# bits2.net
KiCad netlist of a schematic drawn in EAGLE
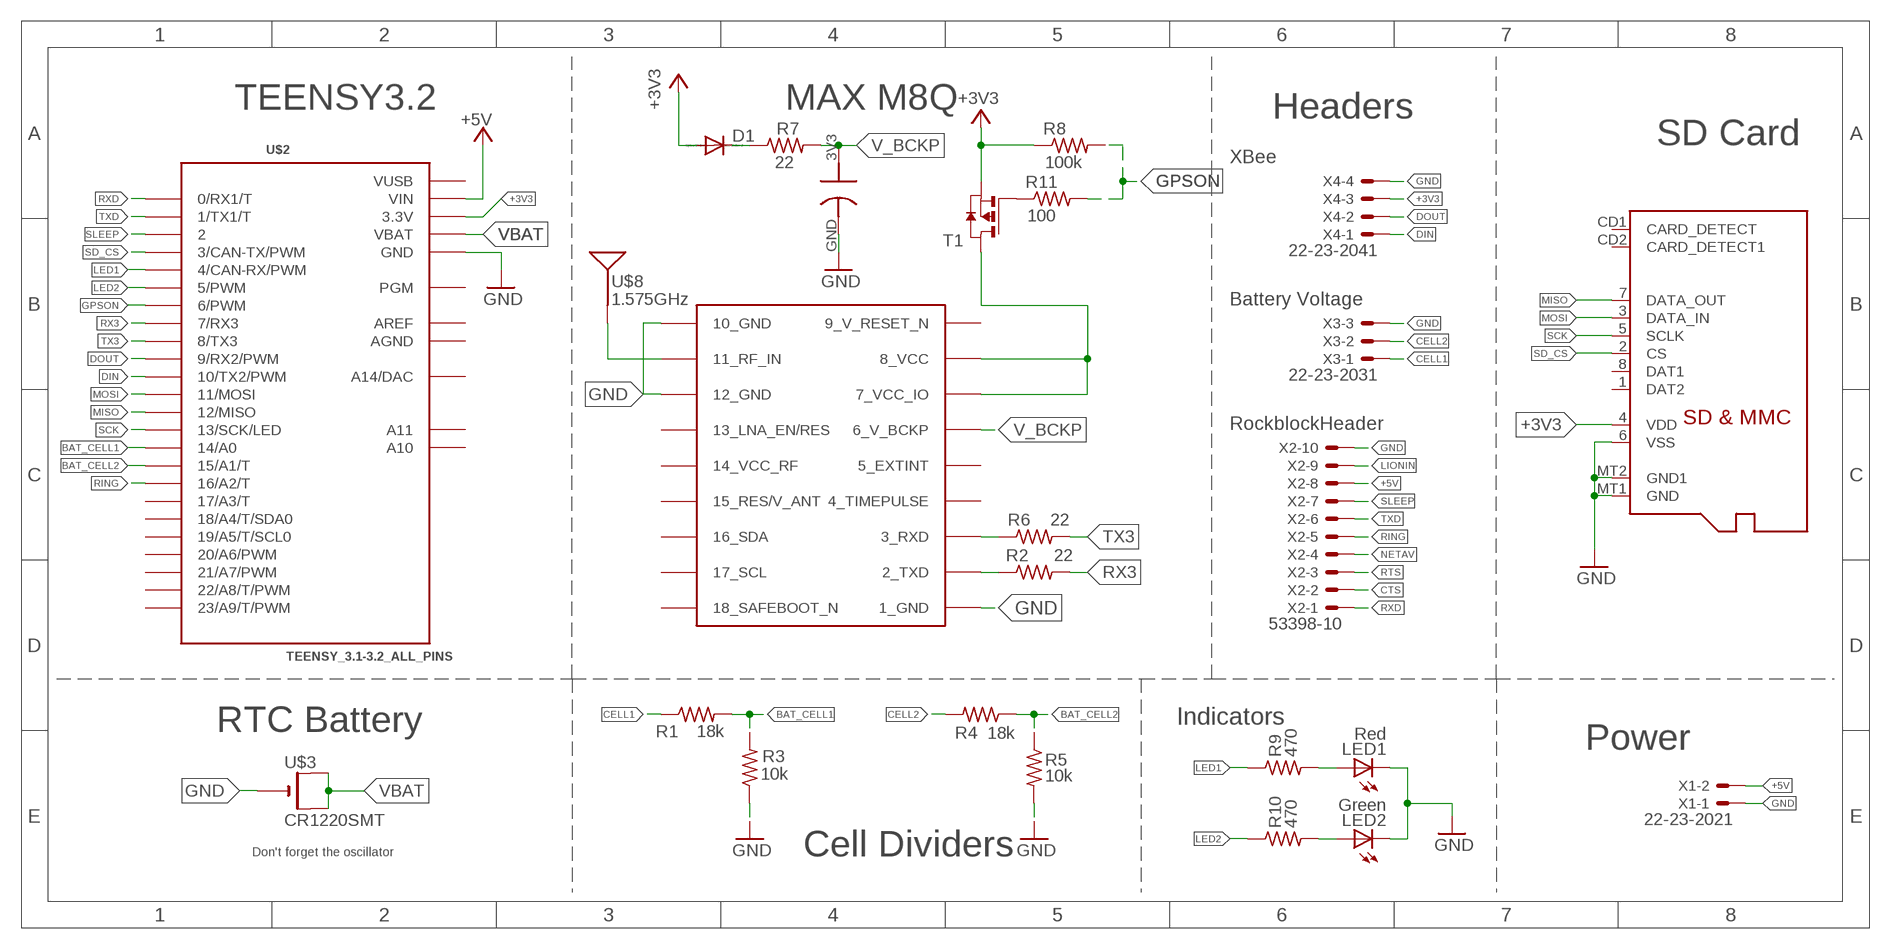
[diagram p0: schematic, sheet 1]

(export (version "E")
  (design (tool "Eeschema 10.0.6"))
  (components
    (comp (ref "C1")
      (value "DCK-3R3E204T614-E")
      (footprint "eagle-import:ELNASUPERCAP")
      (libsource (lib "eagle-import") (part "DCK-3R3E204T614-E"))
    )
    (comp (ref "D1")
      (value "DIODE-SOD523")
      (footprint "eagle-import:SOD523")
      (libsource (lib "eagle-import") (part "DIODE-SOD523"))
    )
    (comp (ref "LED1")
      (value "Red")
      (footprint "eagle-import:CHIP-LED0603")
      (libsource (lib "eagle-import") (part "LEDCHIP-LED0603"))
    )
    (comp (ref "LED2")
      (value "Green")
      (footprint "eagle-import:CHIP-LED0603")
      (libsource (lib "eagle-import") (part "LEDCHIP-LED0603"))
    )
    (comp (ref "R1")
      (value "18k")
      (footprint "eagle-import:R0603")
      (libsource (lib "eagle-import") (part "resistor_348_R-US_R0603"))
    )
    (comp (ref "R2")
      (value "22")
      (footprint "eagle-import:R0603")
      (libsource (lib "eagle-import") (part "R-US_R0603"))
    )
    (comp (ref "R3")
      (value "10k")
      (footprint "eagle-import:R0603")
      (libsource (lib "eagle-import") (part "resistor_348_R-US_R0603"))
    )
    (comp (ref "R4")
      (value "18k")
      (footprint "eagle-import:R0603")
      (libsource (lib "eagle-import") (part "resistor_348_R-US_R0603"))
    )
    (comp (ref "R5")
      (value "10k")
      (footprint "eagle-import:R0603")
      (libsource (lib "eagle-import") (part "resistor_348_R-US_R0603"))
    )
    (comp (ref "R6")
      (value "22")
      (footprint "eagle-import:R0603")
      (libsource (lib "eagle-import") (part "R-US_R0603"))
    )
    (comp (ref "R7")
      (value "22")
      (footprint "eagle-import:R0603")
      (libsource (lib "eagle-import") (part "R-US_R0603"))
    )
    (comp (ref "R8")
      (value "100k")
      (footprint "eagle-import:R0603")
      (libsource (lib "eagle-import") (part "R-US_R0603"))
    )
    (comp (ref "R9")
      (value "470")
      (footprint "eagle-import:R0603")
      (libsource (lib "eagle-import") (part "resistor_348_R-US_R0603"))
    )
    (comp (ref "R10")
      (value "470")
      (footprint "eagle-import:R0603")
      (libsource (lib "eagle-import") (part "resistor_348_R-US_R0603"))
    )
    (comp (ref "R11")
      (value "100")
      (footprint "eagle-import:R0603")
      (libsource (lib "eagle-import") (part "R-US_R0603"))
    )
    (comp (ref "T1")
      (value "PMOSSOT23")
      (footprint "eagle-import:SOT-23")
      (libsource (lib "eagle-import") (part "PMOSSOT23"))
    )
    (comp (ref "U$1")
      (value "MICROSD")
      (footprint "eagle-import:MICROSD")
      (libsource (lib "eagle-import") (part "MICROSD"))
    )
    (comp (ref "U$2")
      (value "TEENSY_3.1-3.2_ALL_PINS")
      (footprint "eagle-import:TEENSY_3.0-3.2&LC_ALL_PINS")
      (libsource (lib "eagle-import") (part "TEENSY_3.1-3.2_ALL_PINS"))
    )
    (comp (ref "U$3")
      (value "CR1220SMT")
      (footprint "eagle-import:CR1220-SMD")
      (libsource (lib "eagle-import") (part "CR1220SMT"))
    )
    (comp (ref "U$7")
      (value "MAX-M8")
      (footprint "eagle-import:MAX-M8")
      (libsource (lib "eagle-import") (part "MAX-M8"))
    )
    (comp (ref "U$8")
      (value "1.575GHz")
      (footprint "eagle-import:SPARKFUN-GPS_ANT-GPS-2X7MM")
      (libsource (lib "eagle-import") (part "SPARKFUN-GPS_ANTENNAGPS-2X7MM"))
    )
    (comp (ref "X1")
      (value "22-23-2021")
      (footprint "eagle-import:22-23-2021")
      (fields (field (name "MF") "MOLEX"))
      (libsource (lib "eagle-import") (part "22-23-2021"))
    )
    (comp (ref "X2")
      (value "53398-10")
      (footprint "eagle-import:53398-10")
      (fields (field (name "MF") "MOLEX") (field (name "MPN") "53398-1071"))
      (libsource (lib "eagle-import") (part "53?-10398"))
    )
    (comp (ref "X3")
      (value "22-23-2031")
      (footprint "eagle-import:22-23-2031")
      (fields (field (name "MF") "MOLEX"))
      (libsource (lib "eagle-import") (part "22-23-2031"))
    )
    (comp (ref "X4")
      (value "22-23-2041")
      (footprint "eagle-import:22-23-2041")
      (fields (field (name "MF") "MOLEX"))
      (libsource (lib "eagle-import") (part "22-23-2041"))
    )
  )
  (nets
    (net (code "1") (name "+3V3") (class "Default")
      (node (ref "D1") (pin "A") (pinfunction "A_A") (pintype "passive"))
      (node (ref "R8") (pin "1") (pinfunction "1_1") (pintype "passive"))
      (node (ref "T1") (pin "2") (pinfunction "S_2") (pintype "passive"))
      (node (ref "U$1") (pin "4") (pinfunction "VDD_4") (pintype "power_in"))
      (node (ref "U$2") (pin "3.3V") (pinfunction "3.3V_3.3V") (pintype "power_in"))
      (node (ref "U$2") (pin "3.3V1") (pinfunction "3.3V_3.3V1") (pintype "power_in"))
      (node (ref "X4") (pin "3") (pinfunction "S_3") (pintype "passive"))
    )
    (net (code "2") (name "+5V") (class "Default")
      (node (ref "U$2") (pin "VIN") (pinfunction "VIN_VIN") (pintype "power_in"))
      (node (ref "X1") (pin "2") (pinfunction "S_2") (pintype "passive"))
      (node (ref "X2") (pin "8") (pinfunction "S_8") (pintype "passive"))
    )
    (net (code "3") (name "/9_V_RESET_N") (class "Default")
      (node (ref "U$7") (pin "9_RESET_N") (pinfunction "9_V_RESET_N_9_RESET_N") (pintype "power_in"))
    )
    (net (code "4") (name "/AGND") (class "Default")
      (node (ref "U$2") (pin "AGND") (pinfunction "AGND_AGND") (pintype "power_in"))
    )
    (net (code "5") (name "/AREF") (class "Default")
      (node (ref "U$2") (pin "AREF") (pinfunction "AREF_AREF") (pintype "power_in"))
    )
    (net (code "6") (name "/VUSB") (class "Default")
      (node (ref "U$2") (pin "VUSB") (pinfunction "VUSB_VUSB") (pintype "power_in"))
    )
    (net (code "7") (name "BAT_CELL1") (class "Default")
      (node (ref "R1") (pin "2") (pinfunction "2_2") (pintype "passive"))
      (node (ref "R3") (pin "2") (pinfunction "2_2") (pintype "passive"))
      (node (ref "U$2") (pin "14/A0") (pinfunction "14/A0_14/A0") (pintype "bidirectional"))
    )
    (net (code "8") (name "BAT_CELL2") (class "Default")
      (node (ref "R4") (pin "1") (pinfunction "1_1") (pintype "passive"))
      (node (ref "R5") (pin "1") (pinfunction "1_1") (pintype "passive"))
      (node (ref "U$2") (pin "15/A1") (pinfunction "15/A1/T_15/A1") (pintype "bidirectional"))
    )
    (net (code "9") (name "CELL1") (class "Default")
      (node (ref "R1") (pin "1") (pinfunction "1_1") (pintype "passive"))
      (node (ref "X3") (pin "1") (pinfunction "S_1") (pintype "passive"))
    )
    (net (code "10") (name "CELL2") (class "Default")
      (node (ref "R4") (pin "2") (pinfunction "2_2") (pintype "passive"))
      (node (ref "X3") (pin "2") (pinfunction "S_2") (pintype "passive"))
    )
    (net (code "11") (name "CTS") (class "Default")
      (node (ref "X2") (pin "2") (pinfunction "S_2") (pintype "passive"))
    )
    (net (code "12") (name "DIN") (class "Default")
      (node (ref "U$2") (pin "10") (pinfunction "10/TX2/PWM_10") (pintype "bidirectional"))
      (node (ref "X4") (pin "1") (pinfunction "S_1") (pintype "passive"))
    )
    (net (code "13") (name "DOUT") (class "Default")
      (node (ref "U$2") (pin "9") (pinfunction "9/RX2/PWM_9") (pintype "bidirectional"))
      (node (ref "X4") (pin "2") (pinfunction "S_2") (pintype "passive"))
    )
    (net (code "14") (name "GND") (class "Default")
      (node (ref "C1") (pin "GND") (pinfunction "GND_GND") (pintype "bidirectional"))
      (node (ref "LED1") (pin "C") (pinfunction "C_C") (pintype "passive"))
      (node (ref "LED2") (pin "C") (pinfunction "C_C") (pintype "passive"))
      (node (ref "R3") (pin "1") (pinfunction "1_1") (pintype "passive"))
      (node (ref "R5") (pin "2") (pinfunction "2_2") (pintype "passive"))
      (node (ref "U$1") (pin "6") (pinfunction "VSS_6") (pintype "power_in"))
      (node (ref "U$1") (pin "MT1") (pinfunction "GND_MT1") (pintype "power_in"))
      (node (ref "U$1") (pin "MT2") (pinfunction "GND1_MT2") (pintype "power_in"))
      (node (ref "U$2") (pin "GND") (pinfunction "GND_GND") (pintype "power_in"))
      (node (ref "U$2") (pin "GND1") (pinfunction "GND_GND1") (pintype "power_in"))
      (node (ref "U$3") (pin "-") (pinfunction "-_-") (pintype "passive"))
      (node (ref "U$7") (pin "10_GND") (pinfunction "10_GND_10_GND") (pintype "power_in"))
      (node (ref "U$7") (pin "12_GND") (pinfunction "12_GND_12_GND") (pintype "power_in"))
      (node (ref "U$7") (pin "1_GND") (pinfunction "1_GND_1_GND") (pintype "power_in"))
      (node (ref "X1") (pin "1") (pinfunction "S_1") (pintype "passive"))
      (node (ref "X2") (pin "10") (pinfunction "S_10") (pintype "passive"))
      (node (ref "X3") (pin "3") (pinfunction "S_3") (pintype "passive"))
      (node (ref "X4") (pin "4") (pinfunction "S_4") (pintype "passive"))
    )
    (net (code "15") (name "GPSON") (class "Default")
      (node (ref "R11") (pin "2") (pinfunction "2_2") (pintype "passive"))
      (node (ref "R8") (pin "2") (pinfunction "2_2") (pintype "passive"))
      (node (ref "U$2") (pin "6") (pinfunction "6/PWM_6") (pintype "bidirectional"))
    )
    (net (code "16") (name "LED1") (class "Default")
      (node (ref "R9") (pin "1") (pinfunction "1_1") (pintype "passive"))
      (node (ref "U$2") (pin "4") (pinfunction "4/CAN-RX/PWM_4") (pintype "bidirectional"))
    )
    (net (code "17") (name "LED2") (class "Default")
      (node (ref "R10") (pin "1") (pinfunction "1_1") (pintype "passive"))
      (node (ref "U$2") (pin "5") (pinfunction "5/PWM_5") (pintype "bidirectional"))
    )
    (net (code "18") (name "LIONIN") (class "Default")
      (node (ref "X2") (pin "9") (pinfunction "S_9") (pintype "passive"))
    )
    (net (code "19") (name "MISO") (class "Default")
      (node (ref "U$1") (pin "7") (pinfunction "DATA_OUT_7") (pintype "output"))
      (node (ref "U$2") (pin "12") (pinfunction "12/MISO_12") (pintype "bidirectional"))
    )
    (net (code "20") (name "MOSI") (class "Default")
      (node (ref "U$1") (pin "3") (pinfunction "DATA_IN_3") (pintype "input"))
      (node (ref "U$2") (pin "11") (pinfunction "11/MOSI_11") (pintype "bidirectional"))
    )
    (net (code "21") (name "NETAV") (class "Default")
      (node (ref "X2") (pin "4") (pinfunction "S_4") (pintype "passive"))
    )
    (net (code "22") (name "Net-(D1-PadC)") (class "Default")
      (node (ref "D1") (pin "C") (pinfunction "C_C") (pintype "passive"))
      (node (ref "R7") (pin "1") (pinfunction "1_1") (pintype "passive"))
    )
    (net (code "23") (name "Net-(LED1-PadA)") (class "Default")
      (node (ref "LED1") (pin "A") (pinfunction "A_A") (pintype "passive"))
      (node (ref "R9") (pin "2") (pinfunction "2_2") (pintype "passive"))
    )
    (net (code "24") (name "Net-(LED2-PadA)") (class "Default")
      (node (ref "LED2") (pin "A") (pinfunction "A_A") (pintype "passive"))
      (node (ref "R10") (pin "2") (pinfunction "2_2") (pintype "passive"))
    )
    (net (code "25") (name "Net-(R2-Pad1)") (class "Default")
      (node (ref "R2") (pin "1") (pinfunction "1_1") (pintype "passive"))
      (node (ref "U$7") (pin "2_TXD") (pinfunction "2_TXD_2_TXD") (pintype "bidirectional"))
    )
    (net (code "26") (name "Net-(R6-Pad1)") (class "Default")
      (node (ref "R6") (pin "1") (pinfunction "1_1") (pintype "passive"))
      (node (ref "U$7") (pin "3_RXD") (pinfunction "3_RXD_3_RXD") (pintype "bidirectional"))
    )
    (net (code "27") (name "Net-(T1-D)") (class "Default")
      (node (ref "T1") (pin "1") (pinfunction "D_1") (pintype "passive"))
      (node (ref "U$7") (pin "7_VCC_IO") (pinfunction "7_VCC_IO_7_VCC_IO") (pintype "power_in"))
      (node (ref "U$7") (pin "8_VCC") (pinfunction "8_VCC_8_VCC") (pintype "power_in"))
    )
    (net (code "28") (name "Net-(T1-G)") (class "Default")
      (node (ref "R11") (pin "1") (pinfunction "1_1") (pintype "passive"))
      (node (ref "T1") (pin "3") (pinfunction "G_3") (pintype "passive"))
    )
    (net (code "29") (name "Net-(U$8-SIGNAL)") (class "Default")
      (node (ref "U$7") (pin "11_RF_IN") (pinfunction "11_RF_IN_11_RF_IN") (pintype "bidirectional"))
      (node (ref "U$8") (pin "1") (pinfunction "SIGNAL_1") (pintype "bidirectional"))
    )
    (net (code "30") (name "RING") (class "Default")
      (node (ref "U$2") (pin "16/A2") (pinfunction "16/A2/T_16/A2") (pintype "bidirectional"))
      (node (ref "X2") (pin "5") (pinfunction "S_5") (pintype "passive"))
    )
    (net (code "31") (name "RTS") (class "Default")
      (node (ref "X2") (pin "3") (pinfunction "S_3") (pintype "passive"))
    )
    (net (code "32") (name "RX3") (class "Default")
      (node (ref "R2") (pin "2") (pinfunction "2_2") (pintype "passive"))
      (node (ref "U$2") (pin "7") (pinfunction "7/RX3_7") (pintype "bidirectional"))
    )
    (net (code "33") (name "RXD") (class "Default")
      (node (ref "U$2") (pin "0") (pinfunction "0/RX1/T_0") (pintype "bidirectional"))
      (node (ref "X2") (pin "1") (pinfunction "S_1") (pintype "passive"))
    )
    (net (code "34") (name "SCK") (class "Default")
      (node (ref "U$1") (pin "5") (pinfunction "SCLK_5") (pintype "input"))
      (node (ref "U$2") (pin "13") (pinfunction "13/SCK/LED_13") (pintype "bidirectional"))
    )
    (net (code "35") (name "SD_CS") (class "Default")
      (node (ref "U$1") (pin "2") (pinfunction "CS_2") (pintype "input"))
      (node (ref "U$2") (pin "3") (pinfunction "3/CAN-TX/PWM_3") (pintype "bidirectional"))
    )
    (net (code "36") (name "SLEEP") (class "Default")
      (node (ref "U$2") (pin "2") (pinfunction "2_2") (pintype "bidirectional"))
      (node (ref "X2") (pin "7") (pinfunction "S_7") (pintype "passive"))
    )
    (net (code "37") (name "TX3") (class "Default")
      (node (ref "R6") (pin "2") (pinfunction "2_2") (pintype "passive"))
      (node (ref "U$2") (pin "8") (pinfunction "8/TX3_8") (pintype "bidirectional"))
    )
    (net (code "38") (name "TXD") (class "Default")
      (node (ref "U$2") (pin "1") (pinfunction "1/TX1/T_1") (pintype "bidirectional"))
      (node (ref "X2") (pin "6") (pinfunction "S_6") (pintype "passive"))
    )
    (net (code "39") (name "VBAT") (class "Default")
      (node (ref "U$2") (pin "VBAT") (pinfunction "VBAT_VBAT") (pintype "power_in"))
      (node (ref "U$3") (pin "+$1") (pinfunction "+_+$1") (pintype "passive"))
      (node (ref "U$3") (pin "+$2") (pinfunction "+1_+$2") (pintype "passive"))
    )
    (net (code "40") (name "V_BCKP") (class "Default")
      (node (ref "C1") (pin "3V3") (pinfunction "3V3_3V3") (pintype "bidirectional"))
      (node (ref "R7") (pin "2") (pinfunction "2_2") (pintype "passive"))
      (node (ref "U$7") (pin "6_V_BCKP") (pinfunction "6_V_BCKP_6_V_BCKP") (pintype "bidirectional"))
    )
    (net (code "41") (name "unconnected-(U$1-CARD_DETECT-PadCD1)") (class "Default")
      (node (ref "U$1") (pin "CD1") (pinfunction "CARD_DETECT_CD1") (pintype "passive"))
    )
    (net (code "42") (name "unconnected-(U$1-CARD_DETECT1-PadCD2)") (class "Default")
      (node (ref "U$1") (pin "CD2") (pinfunction "CARD_DETECT1_CD2") (pintype "passive"))
    )
    (net (code "43") (name "unconnected-(U$1-DAT1-Pad8)") (class "Default")
      (node (ref "U$1") (pin "8") (pinfunction "DAT1_8") (pintype "bidirectional"))
    )
    (net (code "44") (name "unconnected-(U$1-DAT2-Pad1)") (class "Default")
      (node (ref "U$1") (pin "1") (pinfunction "DAT2_1") (pintype "bidirectional"))
    )
    (net (code "45") (name "unconnected-(U$2-17{slash}A3{slash}T-Pad17{slash}A3)") (class "Default")
      (node (ref "U$2") (pin "17/A3") (pinfunction "17/A3/T_17/A3") (pintype "bidirectional"))
    )
    (net (code "46") (name "unconnected-(U$2-18{slash}A4{slash}T{slash}SDA0-Pad18{slash}A4)") (class "Default")
      (node (ref "U$2") (pin "18/A4") (pinfunction "18/A4/T/SDA0_18/A4") (pintype "bidirectional"))
    )
    (net (code "47") (name "unconnected-(U$2-19{slash}A5{slash}T{slash}SCL0-Pad19{slash}A5)") (class "Default")
      (node (ref "U$2") (pin "19/A5") (pinfunction "19/A5/T/SCL0_19/A5") (pintype "bidirectional"))
    )
    (net (code "48") (name "unconnected-(U$2-20{slash}A6{slash}PWM-Pad20{slash}A6)") (class "Default")
      (node (ref "U$2") (pin "20/A6") (pinfunction "20/A6/PWM_20/A6") (pintype "bidirectional"))
    )
    (net (code "49") (name "unconnected-(U$2-21{slash}A7{slash}PWM-Pad21{slash}A7)") (class "Default")
      (node (ref "U$2") (pin "21/A7") (pinfunction "21/A7/PWM_21/A7") (pintype "bidirectional"))
    )
    (net (code "50") (name "unconnected-(U$2-22{slash}A8{slash}T{slash}PWM-Pad22{slash}A8)") (class "Default")
      (node (ref "U$2") (pin "22/A8") (pinfunction "22/A8/T/PWM_22/A8") (pintype "bidirectional"))
    )
    (net (code "51") (name "unconnected-(U$2-23{slash}A9{slash}T{slash}PWM-Pad23{slash}A9)") (class "Default")
      (node (ref "U$2") (pin "23/A9") (pinfunction "23/A9/T/PWM_23/A9") (pintype "bidirectional"))
    )
    (net (code "52") (name "unconnected-(U$2-A14{slash}DAC-PadRESET{slash}DAC)") (class "Default")
      (node (ref "U$2") (pin "RESET/DAC") (pinfunction "A14/DAC_RESET/DAC") (pintype "bidirectional"))
    )
    (net (code "53") (name "unconnected-(U$2-PadA10)") (class "Default")
      (node (ref "U$2") (pin "A10") (pinfunction "A10_A10") (pintype "bidirectional"))
    )
    (net (code "54") (name "unconnected-(U$2-PadA11)") (class "Default")
      (node (ref "U$2") (pin "A11") (pinfunction "A11_A11") (pintype "bidirectional"))
    )
    (net (code "55") (name "unconnected-(U$2-PadPGM)") (class "Default")
      (node (ref "U$2") (pin "PGM") (pinfunction "PGM_PGM") (pintype "bidirectional"))
    )
    (net (code "56") (name "unconnected-(U$7-13_LNA_EN{slash}RES-Pad13_LNA_EN)") (class "Default")
      (node (ref "U$7") (pin "13_LNA_EN") (pinfunction "13_LNA_EN/RES_13_LNA_EN") (pintype "bidirectional"))
    )
    (net (code "57") (name "unconnected-(U$7-15_RES{slash}V_ANT-Pad15_V_ANT{slash}RESERVED)") (class "Default")
      (node (ref "U$7") (pin "15_V_ANT/RESERVED") (pinfunction "15_RES/V_ANT_15_V_ANT/RESERVED") (pintype "bidirectional"))
    )
    (net (code "58") (name "unconnected-(U$7-Pad4_TIMEPULSE)") (class "Default")
      (node (ref "U$7") (pin "4_TIMEPULSE") (pinfunction "4_TIMEPULSE_4_TIMEPULSE") (pintype "bidirectional"))
    )
    (net (code "59") (name "unconnected-(U$7-Pad5_EXTINT)") (class "Default")
      (node (ref "U$7") (pin "5_EXTINT") (pinfunction "5_EXTINT_5_EXTINT") (pintype "bidirectional"))
    )
    (net (code "60") (name "unconnected-(U$7-Pad14_VCC_RF)") (class "Default")
      (node (ref "U$7") (pin "14_VCC_RF") (pinfunction "14_VCC_RF_14_VCC_RF") (pintype "bidirectional"))
    )
    (net (code "61") (name "unconnected-(U$7-Pad16_SDA)") (class "Default")
      (node (ref "U$7") (pin "16_SDA") (pinfunction "16_SDA_16_SDA") (pintype "bidirectional"))
    )
    (net (code "62") (name "unconnected-(U$7-Pad17_SCL)") (class "Default")
      (node (ref "U$7") (pin "17_SCL") (pinfunction "17_SCL_17_SCL") (pintype "bidirectional"))
    )
    (net (code "63") (name "unconnected-(U$7-Pad18_SAFEBOOT_N)") (class "Default")
      (node (ref "U$7") (pin "18_SAFEBOOT_N") (pinfunction "18_SAFEBOOT_N_18_SAFEBOOT_N") (pintype "bidirectional"))
    )
  )
)
